# TELM0002ADC.net
KiCad netlist of a schematic drawn in Altium Designer
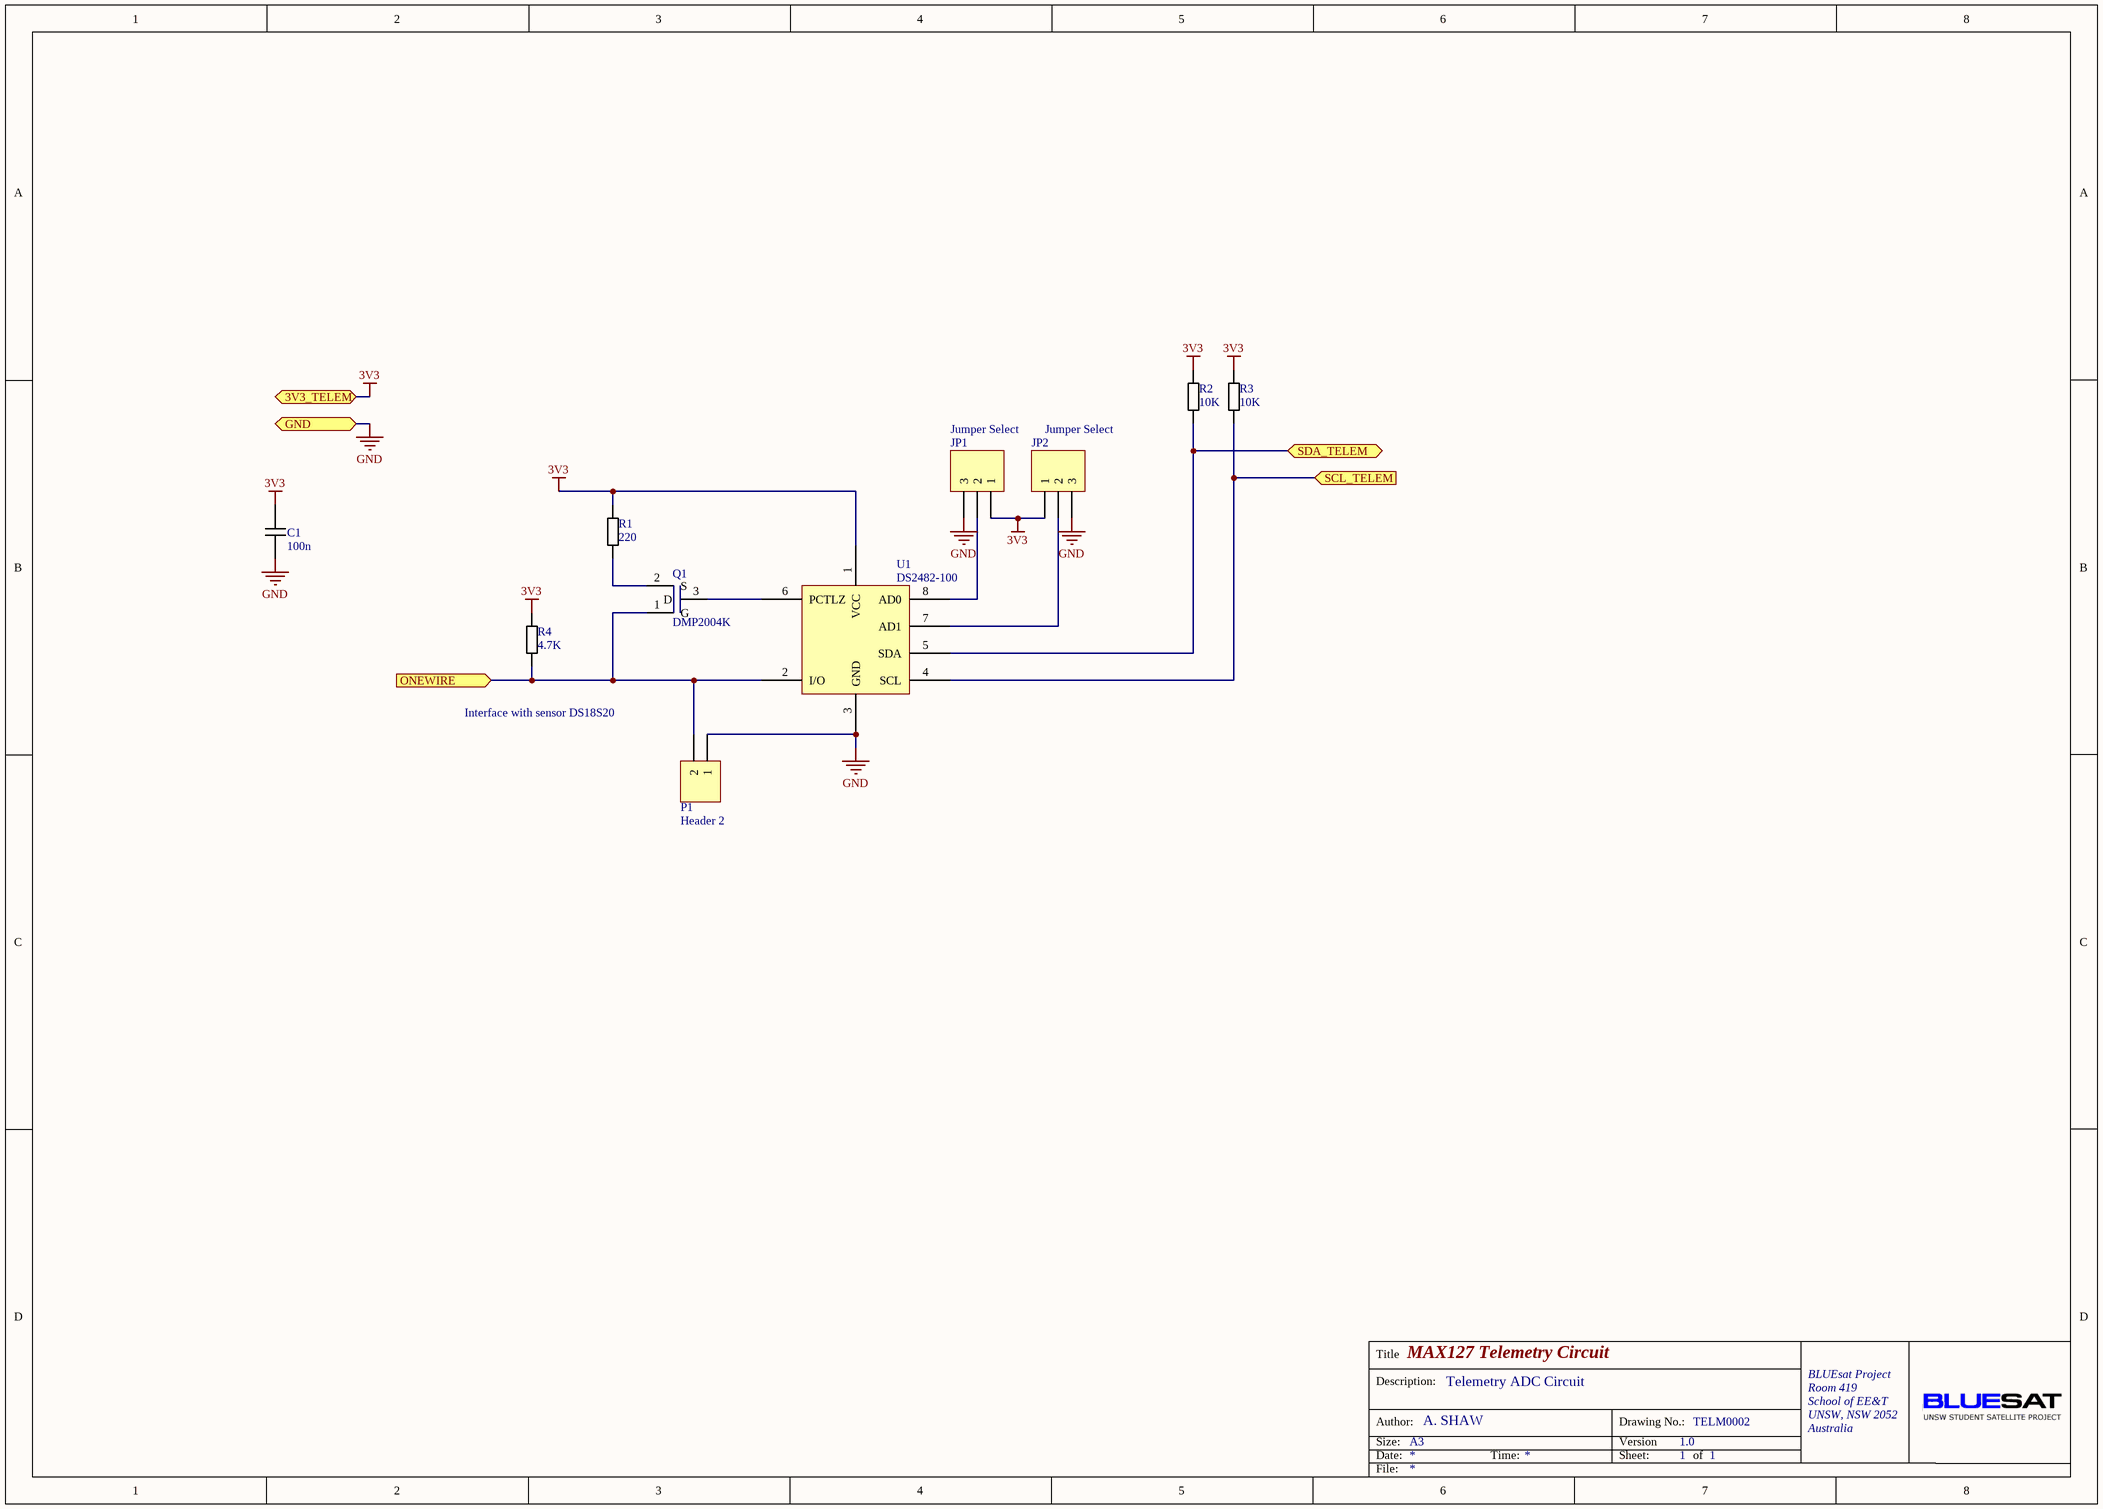
[diagram p0: TELM0002ADC.SchDoc]

(export (version "E")
  (design (tool "Eeschema 10.0.6"))
  (components
    (comp (ref "C1")
      (value "100n")
      (footprint "0805 Cap")
      (description "0805 MLCC - X7R, 10%")
      (fields (field (name "MANUFACTURER") "Kit") (field (name "Comment") "0805 Cap"))
      (libsource (lib "Tray 1 Expansion Board Prototype") (part "0805 MLCC - X7R, 10%"))
    )
    (comp (ref "JP1")
      (value "Jumper Select")
      (footprint "SOLDER_JUMPER_3_A")
      (description "Header, 3-Pin")
      (libsource (lib "Tray 1 Expansion Board Prototype") (part "Header 3"))
    )
    (comp (ref "JP2")
      (value "Jumper Select")
      (footprint "SOLDER_JUMPER_3_A")
      (description "Header, 3-Pin")
      (libsource (lib "") (part "Header 3_1"))
    )
    (comp (ref "P1")
      (value "Header 2")
      (footprint "HDR1X2")
      (description "Header, 2-Pin")
      (libsource (lib "Tray 1 Expansion Board Prototype") (part "Header 2"))
    )
    (comp (ref "Q1")
      (value "DMP2004K")
      (footprint "DMP2004KDITR-ND")
      (description "MOSFET P-CH 20V 600MA SOT23-3")
      (libsource (lib "Tray 1 Expansion Board Prototype") (part "DMP2004K"))
    )
    (comp (ref "R1")
      (value "220")
      (footprint "0805 Resistor")
      (description "0805 Thick Film Resistor 1%")
      (fields (field (name "MANUFACTURER") "Kit") (field (name "Comment") "0805 Resistor"))
      (libsource (lib "Tray 1 Expansion Board Prototype") (part "0805 Thick Film Resistor 1%"))
    )
    (comp (ref "R2")
      (value "10K")
      (footprint "0805 Resistor")
      (description "0805 Thick Film Resistor 1%")
      (fields (field (name "MANUFACTURER") "Kit") (field (name "Comment") "0805 Resistor"))
      (libsource (lib "Tray 1 Expansion Board Prototype") (part "0805 Thick Film Resistor 1%"))
    )
    (comp (ref "R3")
      (value "10K")
      (footprint "0805 Resistor")
      (description "0805 Thick Film Resistor 1%")
      (fields (field (name "MANUFACTURER") "Kit") (field (name "Comment") "0805 Resistor"))
      (libsource (lib "Tray 1 Expansion Board Prototype") (part "0805 Thick Film Resistor 1%"))
    )
    (comp (ref "R4")
      (value "4.7K")
      (footprint "0805 Resistor")
      (description "0805 Thick Film Resistor 1%")
      (fields (field (name "MANUFACTURER") "Kit") (field (name "Comment") "0805 Resistor"))
      (libsource (lib "Tray 1 Expansion Board Prototype") (part "0603 Thick Film Resistor 1%"))
    )
    (comp (ref "U1")
      (value "DS2482-100")
      (footprint "DS2482-100")
      (description "I2C to 1-Wire Master")
      (libsource (lib "Tray 1 Expansion Board Prototype") (part "DS2482-100"))
    )
  )
  (nets
    (net (code "1") (name "/ONEWIRE") (class "Default")
      (node (ref "P1") (pin "2") (pinfunction "2_2") (pintype "passive"))
      (node (ref "Q1") (pin "1") (pinfunction "G_1") (pintype "passive"))
      (node (ref "R4") (pin "1") (pinfunction "1_1") (pintype "passive"))
      (node (ref "U1") (pin "2") (pinfunction "I/O_2") (pintype "passive"))
    )
    (net (code "2") (name "/SCL_TELEM") (class "Default")
      (node (ref "R3") (pin "1") (pinfunction "1_1") (pintype "passive"))
      (node (ref "U1") (pin "4") (pinfunction "SCL_4") (pintype "passive"))
    )
    (net (code "3") (name "/SDA_TELEM") (class "Default")
      (node (ref "R2") (pin "1") (pinfunction "1_1") (pintype "passive"))
      (node (ref "U1") (pin "5") (pinfunction "SDA_5") (pintype "passive"))
    )
    (net (code "4") (name "3V3") (class "Default")
      (node (ref "C1") (pin "2") (pinfunction "2_2") (pintype "passive"))
      (node (ref "JP1") (pin "1") (pinfunction "1_1") (pintype "passive"))
      (node (ref "JP2") (pin "1") (pinfunction "1_1") (pintype "passive"))
      (node (ref "R1") (pin "2") (pinfunction "2_2") (pintype "passive"))
      (node (ref "R2") (pin "2") (pinfunction "2_2") (pintype "passive"))
      (node (ref "R3") (pin "2") (pinfunction "2_2") (pintype "passive"))
      (node (ref "R4") (pin "2") (pinfunction "2_2") (pintype "passive"))
      (node (ref "U1") (pin "1") (pinfunction "VCC_1") (pintype "passive"))
    )
    (net (code "5") (name "GND") (class "Default")
      (node (ref "C1") (pin "1") (pinfunction "1_1") (pintype "passive"))
      (node (ref "JP1") (pin "3") (pinfunction "3_3") (pintype "passive"))
      (node (ref "JP2") (pin "3") (pinfunction "3_3") (pintype "passive"))
      (node (ref "P1") (pin "1") (pinfunction "1_1") (pintype "passive"))
      (node (ref "U1") (pin "3") (pinfunction "GND_3") (pintype "passive"))
    )
    (net (code "6") (name "Net-(Q1-D)") (class "Default")
      (node (ref "Q1") (pin "3") (pinfunction "D_3") (pintype "passive"))
      (node (ref "U1") (pin "6") (pinfunction "PCTLZ_6") (pintype "passive"))
    )
    (net (code "7") (name "Net-(Q1-S)") (class "Default")
      (node (ref "Q1") (pin "2") (pinfunction "S_2") (pintype "passive"))
      (node (ref "R1") (pin "1") (pinfunction "1_1") (pintype "passive"))
    )
    (net (code "8") (name "Net-(U1-AD0)") (class "Default")
      (node (ref "JP1") (pin "2") (pinfunction "2_2") (pintype "passive"))
      (node (ref "U1") (pin "8") (pinfunction "AD0_8") (pintype "passive"))
    )
    (net (code "9") (name "Net-(U1-AD1)") (class "Default")
      (node (ref "JP2") (pin "2") (pinfunction "2_2") (pintype "passive"))
      (node (ref "U1") (pin "7") (pinfunction "AD1_7") (pintype "passive"))
    )
  )
)
